# Parallel_LED_Strip_Buck_Converter.net
KiCad netlist of a schematic drawn in Altium Designer
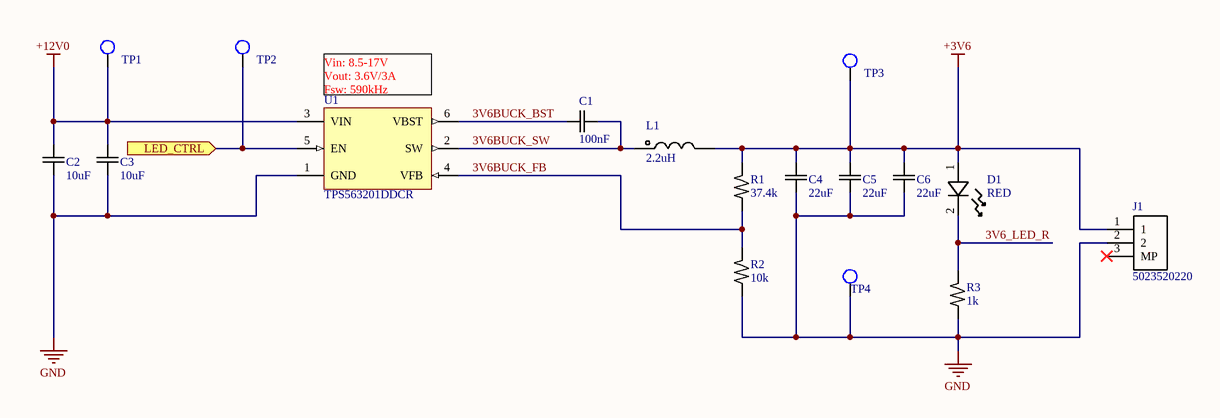
[diagram p0: Parallel LED Strip Buck Converter.SchDoc]

(export (version "E")
  (design (tool "Eeschema 10.0.6"))
  (components
    (comp (ref "C1")
      (value "100nF")
      (footprint "C0603")
      (description "CAP CER 100nF 50V X7R 0603")
      (fields (field (name "MF") "HRE") (field (name "MP") "CGA0603X7R104K500JT"))
      (libsource (lib "Components") (part "Cap_cer"))
    )
    (comp (ref "C2")
      (value "10uF")
      (footprint "C1206")
      (description "CAP CER 10uF 25V X7R 1206")
      (fields (field (name "MF") "SAMWHA") (field (name "MP") "CS3216X7R106K250NRI"))
      (libsource (lib "Components") (part "Cap_cer"))
    )
    (comp (ref "C3")
      (value "10uF")
      (footprint "C1206")
      (description "CAP CER 10uF 25V X7R 1206")
      (fields (field (name "MF") "SAMWHA") (field (name "MP") "CS3216X7R106K250NRI"))
      (libsource (lib "Components") (part "Cap_cer"))
    )
    (comp (ref "C4")
      (value "22uF")
      (footprint "C1206")
      (description "CAP CER 22uF 10V X7R 1206")
      (fields (field (name "MF") "CCTC") (field (name "MP") "TCC1206X7R226K100HT"))
      (libsource (lib "Components") (part "Cap_cer"))
    )
    (comp (ref "C5")
      (value "22uF")
      (footprint "C1206")
      (description "CAP CER 22uF 10V X7R 1206")
      (fields (field (name "MF") "CCTC") (field (name "MP") "TCC1206X7R226K100HT"))
      (libsource (lib "Components") (part "Cap_cer"))
    )
    (comp (ref "C6")
      (value "22uF")
      (footprint "C1206")
      (description "CAP CER 22uF 10V X7R 1206")
      (fields (field (name "MF") "CCTC") (field (name "MP") "TCC1206X7R226K100HT"))
      (libsource (lib "Components") (part "Cap_cer"))
    )
    (comp (ref "D1")
      (value "RED")
      (footprint "LED0805 RED")
      (description "LED RED WATER CLEAR 0805 SMD")
      (fields (field (name "MF") "XINGLIGHT") (field (name "MP") "XL-TD2012SURC"))
      (libsource (lib "Components") (part "LED"))
    )
    (comp (ref "J1")
      (value "5023520220")
      (footprint "5600200220")
      (fields (field (name "MP") "5600200220") (field (name "MF") "MOLEX"))
      (libsource (lib "Connectors") (part "5023520202"))
    )
    (comp (ref "L1")
      (value "2.2uH")
      (footprint "Coil 7.2x6.6")
      (description "FIXED IND 2.2uH 9.5A 11.2mΩ SMD,7.2x6.6mm")
      (fields (field (name "MF") "SHOU HAN") (field (name "MP") "CYA0650-2.2UH"))
      (libsource (lib "Components") (part "Coil"))
    )
    (comp (ref "R1")
      (value "37.4k")
      (footprint "R0603")
      (description "RES 37.4kΩ ±1% 100mW 0603")
      (fields (field (name "MF") "FOJAN") (field (name "MP") "FRC0603F3742TS"))
      (libsource (lib "Components") (part "Res"))
    )
    (comp (ref "R2")
      (value "10k")
      (footprint "R0603")
      (description "RES 10kΩ ±1% 100mW 0603")
      (fields (field (name "MF") "FOJAN") (field (name "MP") "FRC0603F1002TS"))
      (libsource (lib "Components") (part "Res"))
    )
    (comp (ref "R3")
      (value "1k")
      (footprint "R0603")
      (description "RES 1kΩ ±5% 100mW 0603")
      (fields (field (name "MF") "VO") (field (name "MP") "SCR0603J1K"))
      (libsource (lib "Components") (part "Res"))
    )
    (comp (ref "TP1")
      (value "TestPoint")
      (footprint "TESTPOINT_SMD_1.27MM")
      (libsource (lib "Components") (part "TestPoint"))
    )
    (comp (ref "TP2")
      (value "TestPoint")
      (footprint "TESTPOINT_SMD_1.27MM")
      (libsource (lib "Components") (part "TestPoint"))
    )
    (comp (ref "TP3")
      (value "TestPoint")
      (footprint "TESTPOINT_SMD_1.27MM")
      (libsource (lib "Components") (part "TestPoint"))
    )
    (comp (ref "TP4")
      (value "TestPoint")
      (footprint "TESTPOINT_SMD_1.27MM")
      (libsource (lib "Components") (part "TestPoint"))
    )
    (comp (ref "U1")
      (value "TPS563201DDCR")
      (footprint "SOT23-6")
      (fields (field (name "MF") "Texas Instruments"))
      (libsource (lib "Components") (part "TPS563201DDCR"))
    )
  )
  (nets
    (net (code "1") (name "+3V6") (class "Default")
      (node (ref "C4") (pin "1") (pinfunction "1_1") (pintype "passive"))
      (node (ref "C5") (pin "1") (pinfunction "1_1") (pintype "passive"))
      (node (ref "C6") (pin "1") (pinfunction "1_1") (pintype "passive"))
      (node (ref "D1") (pin "1") (pinfunction "1_1") (pintype "passive"))
      (node (ref "J1") (pin "1") (pinfunction "1_1") (pintype "passive"))
      (node (ref "L1") (pin "2") (pinfunction "2_2") (pintype "passive"))
      (node (ref "R1") (pin "2") (pinfunction "2_2") (pintype "passive"))
      (node (ref "TP3") (pin "1") (pinfunction "1_1") (pintype "passive"))
    )
    (net (code "2") (name "+12V0") (class "Default")
      (node (ref "C2") (pin "2") (pinfunction "2_2") (pintype "passive"))
      (node (ref "C3") (pin "2") (pinfunction "2_2") (pintype "passive"))
      (node (ref "TP1") (pin "1") (pinfunction "1_1") (pintype "passive"))
      (node (ref "U1") (pin "3") (pinfunction "VIN_3") (pintype "power_in"))
    )
    (net (code "3") (name "/3V6BUCK_BST") (class "Default")
      (node (ref "C1") (pin "1") (pinfunction "1_1") (pintype "passive"))
      (node (ref "U1") (pin "6") (pinfunction "VBST_6") (pintype "output"))
    )
    (net (code "4") (name "/3V6BUCK_FB") (class "Default")
      (node (ref "R1") (pin "1") (pinfunction "1_1") (pintype "passive"))
      (node (ref "R2") (pin "2") (pinfunction "2_2") (pintype "passive"))
      (node (ref "U1") (pin "4") (pinfunction "VFB_4") (pintype "input"))
    )
    (net (code "5") (name "/3V6BUCK_SW") (class "Default")
      (node (ref "C1") (pin "2") (pinfunction "2_2") (pintype "passive"))
      (node (ref "L1") (pin "1") (pinfunction "1_1") (pintype "passive"))
      (node (ref "U1") (pin "2") (pinfunction "SW_2") (pintype "output"))
    )
    (net (code "6") (name "/3V6_LED_R") (class "Default")
      (node (ref "D1") (pin "2") (pinfunction "2_2") (pintype "passive"))
      (node (ref "R3") (pin "2") (pinfunction "2_2") (pintype "passive"))
    )
    (net (code "7") (name "/LED_CTRL") (class "Default")
      (node (ref "TP2") (pin "1") (pinfunction "1_1") (pintype "passive"))
      (node (ref "U1") (pin "5") (pinfunction "EN_5") (pintype "input"))
    )
    (net (code "8") (name "GND") (class "Default")
      (node (ref "C2") (pin "1") (pinfunction "1_1") (pintype "passive"))
      (node (ref "C3") (pin "1") (pinfunction "1_1") (pintype "passive"))
      (node (ref "C4") (pin "2") (pinfunction "2_2") (pintype "passive"))
      (node (ref "C5") (pin "2") (pinfunction "2_2") (pintype "passive"))
      (node (ref "C6") (pin "2") (pinfunction "2_2") (pintype "passive"))
      (node (ref "J1") (pin "2") (pinfunction "2_2") (pintype "passive"))
      (node (ref "R2") (pin "1") (pinfunction "1_1") (pintype "passive"))
      (node (ref "R3") (pin "1") (pinfunction "1_1") (pintype "passive"))
      (node (ref "TP4") (pin "1") (pinfunction "1_1") (pintype "passive"))
      (node (ref "U1") (pin "1") (pinfunction "GND_1") (pintype "power_in"))
    )
    (net (code "9") (name "unconnected-(J1-MP-Pad3)") (class "Default")
      (node (ref "J1") (pin "3") (pinfunction "MP_3") (pintype "passive+no_connect"))
    )
  )
)
